# ADC_AFE.net
KiCad netlist of a schematic drawn in Altium Designer
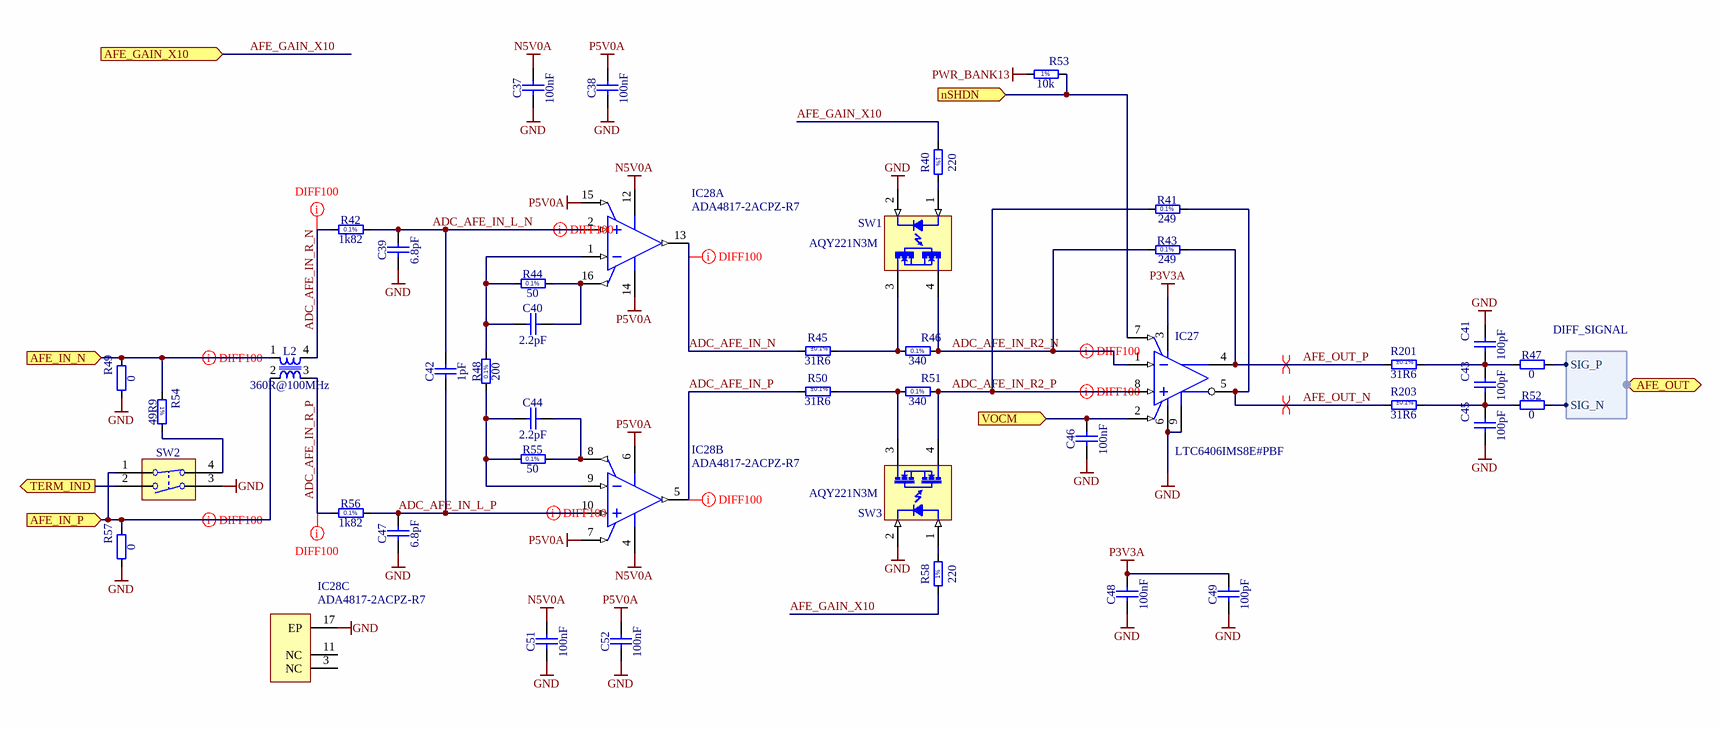
[diagram p0: ADC_AFE.SchDoc]

(export (version "E")
  (design (tool "Eeschema 10.0.6"))
  (components
    (comp (ref "C37")
      (value "100nF")
      (footprint "CAPC1005X55N")
      (description "Non-polarised capacitor")
      (fields
        (field (name "PART NUMBER") "CC0402_100NF_16V_10%_X7R")
        (field (name "VOLTAGE") "16V")
        (field (name "AUTHOR") "CERN DEM JLC")
      )
      (libsource (lib "Capacitors") (part "Capacitor - non polarized"))
    )
    (comp (ref "C38")
      (value "100nF")
      (footprint "CAPC1005X55N")
      (description "Non-polarised capacitor")
      (fields
        (field (name "PART NUMBER") "CC0402_100NF_16V_10%_X7R")
        (field (name "VOLTAGE") "16V")
        (field (name "AUTHOR") "CERN DEM JLC")
      )
      (libsource (lib "Capacitors") (part "Capacitor - non polarized"))
    )
    (comp (ref "C39")
      (value "6.8pF")
      (footprint "CAPC1005X61N")
      (description "Non-polarised capacitor")
      (fields
        (field (name "PART NUMBER") "CC0402_6.8PF_50V_0.1PF_NP0_JOHANSON_R07S")
        (field (name "VOLTAGE") "50V")
        (field (name "AUTHOR") "CERN DEM BC")
      )
      (libsource (lib "Capacitors") (part "Capacitor - non polarized"))
    )
    (comp (ref "C40")
      (value "2.2pF")
      (footprint "CAPC1608X87N")
      (description "Non-polarised capacitor")
      (fields
        (field (name "PART NUMBER") "CC0603_2.2PF_50V_0.25PF_NP0")
        (field (name "VOLTAGE") "50V")
        (field (name "AUTHOR") "CERN DEM JLC")
      )
      (libsource (lib "Capacitors") (part "Capacitor - non polarized"))
    )
    (comp (ref "C41")
      (value "100pF")
      (footprint "CAPC1005X55N")
      (description "Non-polarised capacitor")
      (fields
        (field (name "PART NUMBER") "CC0402_100PF_50V_2%_C0G")
        (field (name "VOLTAGE") "50V")
        (field (name "AUTHOR") "CERN DEM BC")
      )
      (libsource (lib "Capacitors") (part "Capacitor - non polarized"))
    )
    (comp (ref "C42")
      (value "1pF")
      (footprint "CAPC1005X55N")
      (description "Non-polarised capacitor")
      (fields
        (field (name "PART NUMBER") "CC0402_1PF_50V_0.25PF_C0G")
        (field (name "VOLTAGE") "50V")
        (field (name "AUTHOR") "CERN DEM JLC")
      )
      (libsource (lib "Capacitors") (part "Capacitor - non polarized"))
    )
    (comp (ref "C43")
      (value "100pF")
      (footprint "CAPC1005X55N")
      (description "Non-polarised capacitor")
      (fields
        (field (name "PART NUMBER") "CC0402_100PF_50V_2%_C0G")
        (field (name "VOLTAGE") "50V")
        (field (name "AUTHOR") "CERN DEM BC")
      )
      (libsource (lib "Capacitors") (part "Capacitor - non polarized"))
    )
    (comp (ref "C44")
      (value "2.2pF")
      (footprint "CAPC1608X87N")
      (description "Non-polarised capacitor")
      (fields
        (field (name "PART NUMBER") "CC0603_2.2PF_50V_0.25PF_NP0")
        (field (name "VOLTAGE") "50V")
        (field (name "AUTHOR") "CERN DEM JLC")
      )
      (libsource (lib "Capacitors") (part "Capacitor - non polarized"))
    )
    (comp (ref "C45")
      (value "100pF")
      (footprint "CAPC1005X55N")
      (description "Non-polarised capacitor")
      (fields
        (field (name "PART NUMBER") "CC0402_100PF_50V_2%_C0G")
        (field (name "VOLTAGE") "50V")
        (field (name "AUTHOR") "CERN DEM BC")
      )
      (libsource (lib "Capacitors") (part "Capacitor - non polarized"))
    )
    (comp (ref "C46")
      (value "100nF")
      (footprint "CAPC1005X55N")
      (description "Non-polarised capacitor")
      (fields
        (field (name "PART NUMBER") "CC0402_100NF_16V_10%_X7R")
        (field (name "VOLTAGE") "16V")
        (field (name "AUTHOR") "CERN DEM JLC")
      )
      (libsource (lib "Capacitors") (part "Capacitor - non polarized"))
    )
    (comp (ref "C47")
      (value "6.8pF")
      (footprint "CAPC1005X61N")
      (description "Non-polarised capacitor")
      (fields
        (field (name "PART NUMBER") "CC0402_6.8PF_50V_0.1PF_NP0_JOHANSON_R07S")
        (field (name "VOLTAGE") "50V")
        (field (name "AUTHOR") "CERN DEM BC")
      )
      (libsource (lib "Capacitors") (part "Capacitor - non polarized"))
    )
    (comp (ref "C48")
      (value "100nF")
      (footprint "CAPC1005X55N")
      (description "Non-polarised capacitor")
      (fields
        (field (name "PART NUMBER") "CC0402_100NF_16V_10%_X7R")
        (field (name "VOLTAGE") "16V")
        (field (name "AUTHOR") "CERN DEM JLC")
      )
      (libsource (lib "Capacitors") (part "Capacitor - non polarized"))
    )
    (comp (ref "C49")
      (value "100pF")
      (footprint "CAPC1005X55N")
      (description "Non-polarised capacitor")
      (fields
        (field (name "PART NUMBER") "CC0402_100PF_50V_2%_C0G")
        (field (name "VOLTAGE") "50V")
        (field (name "AUTHOR") "CERN DEM BC")
      )
      (libsource (lib "Capacitors") (part "Capacitor - non polarized"))
    )
    (comp (ref "C51")
      (value "100nF")
      (footprint "CAPC1005X55N")
      (description "Non-polarised capacitor")
      (fields
        (field (name "PART NUMBER") "CC0402_100NF_16V_10%_X7R")
        (field (name "VOLTAGE") "16V")
        (field (name "AUTHOR") "CERN DEM JLC")
      )
      (libsource (lib "Capacitors") (part "Capacitor - non polarized"))
    )
    (comp (ref "C52")
      (value "100nF")
      (footprint "CAPC1005X55N")
      (description "Non-polarised capacitor")
      (fields
        (field (name "PART NUMBER") "CC0402_100NF_16V_10%_X7R")
        (field (name "VOLTAGE") "16V")
        (field (name "AUTHOR") "CERN DEM JLC")
      )
      (libsource (lib "Capacitors") (part "Capacitor - non polarized"))
    )
    (comp (ref "IC27")
      (value "LTC6406IMS8E#PBF")
      (footprint "LT-MS8E-8-EDP_M")
      (fields
        (field (name "LINEAR TECHNOLOGY PART NUMBER") "LTC6406")
        (field (name "MANUFACTURER") "Linear Technology")
      )
      (libsource (lib "Altium Content Vault") (part "LT-LTC6406-MS8E-8"))
    )
    (comp (ref "IC28")
      (value "ADA4817-2ACPZ-R7")
      (footprint "CP-16-4_N")
      (fields (field (name "GENERIC PART NUMBER") "ADA4817-2") (field (name "MANUFACTURER") "Analog Devices"))
      (libsource (lib "") (part "ADI-ADA4817-2-CP-16-4_1"))
    )
    (comp (ref "L2")
      (value "360R@100MHz")
      (footprint "IND_TDK_ACM2012")
      (description "Inductor Common Mode")
      (fields
        (field (name "PART NUMBER") "IND_TDK_ACM2012-361-2P")
        (field (name "POWER") "220mA")
        (field (name "AUTHOR") "CERN DEM BC")
      )
      (libsource (lib "Inductors & Transformers") (part "Inductor Common Mode 1-4 2-3"))
    )
    (comp (ref "R40")
      (value "220")
      (footprint "RESC1608X55N")
      (description "Resistor - 1%")
      (fields
        (field (name "MANUFACTURER1 PART NUMBER") "NRC06F2200TRF")
        (field (name "MANUFACTURER") "GENERIC")
        (field (name "AUTHOR") "CERN DEM JLC")
      )
      (libsource (lib "Resistors") (part "Resistor - 1%"))
    )
    (comp (ref "R41")
      (value "249")
      (footprint "RESC1608X55N")
      (description "Resistor - 0.1%")
      (fields
        (field (name "PART NUMBER") "R0603_249R_0.1%_0.063W_10PPM")
        (field (name "POWER") "0.063W")
        (field (name "AUTHOR") "CERN DEM JLC")
      )
      (libsource (lib "") (part "Resistor - 0.1%_1"))
    )
    (comp (ref "R42")
      (value "1k82")
      (footprint "RESC1608X55N")
      (description "Resistor - 0.1%")
      (fields
        (field (name "PART NUMBER") "R0603_1K82_0.1%_0.063W_10PPM")
        (field (name "POWER") "0.063W")
        (field (name "AUTHOR") "CERN DEM JLC")
      )
      (libsource (lib "") (part "Resistor - 0.1%_1"))
    )
    (comp (ref "R43")
      (value "249")
      (footprint "RESC1608X55N")
      (description "Resistor - 0.1%")
      (fields
        (field (name "PART NUMBER") "R0603_249R_0.1%_0.063W_10PPM")
        (field (name "POWER") "0.063W")
        (field (name "AUTHOR") "CERN DEM JLC")
      )
      (libsource (lib "") (part "Resistor - 0.1%_1"))
    )
    (comp (ref "R44")
      (value "50")
      (footprint "RESC1005X35N")
      (description "Resistor - 0.1%")
      (fields
        (field (name "PART NUMBER") "R0402_50R_0.1%_0.05W_25PPM")
        (field (name "POWER") "0.05W")
        (field (name "AUTHOR") "CERN DEM JMW")
      )
      (libsource (lib "Resistors") (part "Resistor - 0.1%"))
    )
    (comp (ref "R45")
      (value "31R6")
      (footprint "RESC1608X55N")
      (description "Resistor - 0.1%")
      (fields
        (field (name "PART NUMBER") "R0603_31R6_0.1%_0.063W_10PPM")
        (field (name "POWER") "0.063W")
        (field (name "TOLERANCE") "±0.1%")
        (field (name "AUTHOR") "CERN DEM JLC")
      )
      (libsource (lib "") (part "Resistor - 0.1%_1"))
    )
    (comp (ref "R46")
      (value "340")
      (footprint "RESC1608X55N")
      (description "Resistor - 0.1%")
      (fields
        (field (name "PART NUMBER") "R0603_340R_0.1%_0.063W_10PPM")
        (field (name "POWER") "0.063W")
        (field (name "AUTHOR") "CERN DEM JLC")
      )
      (libsource (lib "") (part "Resistor - 0.1%_1"))
    )
    (comp (ref "R47")
      (value "0")
      (footprint "RESC1005X40N")
      (description "Resistor")
      (fields
        (field (name "PART NUMBER") "R0402_0R_JUMPER")
        (field (name "MANUFACTURER") "GENERIC")
        (field (name "AUTHOR") "CERN DEM JLC")
      )
      (libsource (lib "Resistors") (part "Resistor"))
    )
    (comp (ref "R48")
      (value "200")
      (footprint "RESC1608X55N")
      (description "Resistor - 0.1%")
      (fields
        (field (name "PART NUMBER") "R0603_200R_0.1%_0.063W_10PPM")
        (field (name "POWER") "0.063W")
        (field (name "AUTHOR") "CERN DEM JLC")
      )
      (libsource (lib "") (part "Resistor - 0.1%_1"))
    )
    (comp (ref "R49")
      (value "0")
      (footprint "RESC1005X40N")
      (description "Resistor")
      (fields
        (field (name "PART NUMBER") "R0402_0R_JUMPER")
        (field (name "MANUFACTURER") "GENERIC")
        (field (name "AUTHOR") "CERN DEM JLC")
      )
      (libsource (lib "Resistors") (part "Resistor"))
    )
    (comp (ref "R50")
      (value "31R6")
      (footprint "RESC1608X55N")
      (description "Resistor - 0.1%")
      (fields
        (field (name "PART NUMBER") "R0603_31R6_0.1%_0.063W_10PPM")
        (field (name "POWER") "0.063W")
        (field (name "TOLERANCE") "±0.1%")
        (field (name "AUTHOR") "CERN DEM JLC")
      )
      (libsource (lib "") (part "Resistor - 0.1%_1"))
    )
    (comp (ref "R51")
      (value "340")
      (footprint "RESC1608X55N")
      (description "Resistor - 0.1%")
      (fields
        (field (name "PART NUMBER") "R0603_340R_0.1%_0.063W_10PPM")
        (field (name "POWER") "0.063W")
        (field (name "AUTHOR") "CERN DEM JLC")
      )
      (libsource (lib "") (part "Resistor - 0.1%_1"))
    )
    (comp (ref "R52")
      (value "0")
      (footprint "RESC1005X40N")
      (description "Resistor")
      (fields
        (field (name "PART NUMBER") "R0402_0R_JUMPER")
        (field (name "MANUFACTURER") "GENERIC")
        (field (name "AUTHOR") "CERN DEM JLC")
      )
      (libsource (lib "Resistors") (part "Resistor"))
    )
    (comp (ref "R53")
      (value "10k")
      (footprint "RESC1005X40N")
      (description "Resistor - 1%")
      (fields
        (field (name "PART NUMBER") "R0402_10K_1%_0.0625W_100PPM")
        (field (name "POWER") "0.0625W")
        (field (name "AUTHOR") "CERN DEM JLC")
      )
      (libsource (lib "Resistors") (part "Resistor - 1%"))
    )
    (comp (ref "R54")
      (value "49R9")
      (footprint "RESC6331X70N")
      (description "Resistor - 1%")
      (fields
        (field (name "PART NUMBER") "R2512_49R9_1%_1W_100PPM_VISHAY_CRCW")
        (field (name "POWER") "1W")
        (field (name "AUTHOR") "CERN DEM JLC")
      )
      (libsource (lib "Resistors") (part "Resistor - 1%"))
    )
    (comp (ref "R55")
      (value "50")
      (footprint "RESC1005X35N")
      (description "Resistor - 0.1%")
      (fields
        (field (name "PART NUMBER") "R0402_50R_0.1%_0.05W_25PPM")
        (field (name "POWER") "0.05W")
        (field (name "AUTHOR") "CERN DEM JMW")
      )
      (libsource (lib "Resistors") (part "Resistor - 0.1%"))
    )
    (comp (ref "R56")
      (value "1k82")
      (footprint "RESC1608X55N")
      (description "Resistor - 0.1%")
      (fields
        (field (name "PART NUMBER") "R0603_1K82_0.1%_0.063W_10PPM")
        (field (name "POWER") "0.063W")
        (field (name "AUTHOR") "CERN DEM JLC")
      )
      (libsource (lib "") (part "Resistor - 0.1%_1"))
    )
    (comp (ref "R57")
      (value "0")
      (footprint "RESC1005X40N")
      (description "Resistor")
      (fields
        (field (name "PART NUMBER") "R0402_0R_JUMPER")
        (field (name "MANUFACTURER") "GENERIC")
        (field (name "AUTHOR") "CERN DEM JLC")
      )
      (libsource (lib "Resistors") (part "Resistor"))
    )
    (comp (ref "R58")
      (value "220")
      (footprint "RESC1608X55N")
      (description "Resistor - 1%")
      (fields
        (field (name "MANUFACTURER1 PART NUMBER") "NRC06F2200TRF")
        (field (name "MANUFACTURER") "GENERIC")
        (field (name "AUTHOR") "CERN DEM JLC")
      )
      (libsource (lib "Resistors") (part "Resistor - 1%"))
    )
    (comp (ref "R201")
      (value "31R6")
      (footprint "RESC1608X55N")
      (description "Resistor - 0.1%")
      (fields
        (field (name "PART NUMBER") "R0603_31R6_0.1%_0.063W_10PPM")
        (field (name "POWER") "0.063W")
        (field (name "TOLERANCE") "±0.1%")
        (field (name "AUTHOR") "CERN DEM JLC")
      )
      (libsource (lib "") (part "Resistor - 0.1%_1"))
    )
    (comp (ref "R203")
      (value "31R6")
      (footprint "RESC1608X55N")
      (description "Resistor - 0.1%")
      (fields
        (field (name "PART NUMBER") "R0603_31R6_0.1%_0.063W_10PPM")
        (field (name "POWER") "0.063W")
        (field (name "TOLERANCE") "±0.1%")
        (field (name "AUTHOR") "CERN DEM JLC")
      )
      (libsource (lib "") (part "Resistor - 0.1%_1"))
    )
    (comp (ref "SW1")
      (value "AQY221N3M")
      (footprint "PANASONIC_AQY22(SON)")
      (description "PhotoMOS Relay")
      (fields (field (name "MANUFACTURER") "PANASONIC") (field (name "AUTHOR") "CERN DEM JLC"))
      (libsource (lib "ICs And Semiconductors") (part "PhotoMOS Relay x1 Type2"))
    )
    (comp (ref "SW2")
      (value "Switch")
      (footprint "SW_CTS_204-121ST")
      (description "2x SPST DIP Switch 1NO + 1NF")
      (fields
        (field (name "PART NUMBER") "SW_CTS_204-121ST")
        (field (name "MANUFACTURER") "CTS")
        (field (name "AUTHOR") "CERN DEM JLC")
      )
      (libsource (lib "Eletro-mechanical") (part "SW_CTS_204-121ST"))
    )
    (comp (ref "SW3")
      (value "AQY221N3M")
      (footprint "PANASONIC_AQY22(SON)")
      (description "PhotoMOS Relay")
      (fields (field (name "MANUFACTURER") "PANASONIC") (field (name "AUTHOR") "CERN DEM JLC"))
      (libsource (lib "") (part "PhotoMOS Relay x1 Type2_1"))
    )
  )
  (nets
    (net (code "2") (name "/ADC_AFE_IN_L_N") (class "Default")
      (node (ref "C39") (pin "2") (pinfunction "2_2") (pintype "passive"))
      (node (ref "C42") (pin "2") (pinfunction "2_2") (pintype "passive"))
      (node (ref "IC28") (pin "2") (pinfunction "+IN_1_2") (pintype "input"))
      (node (ref "R42") (pin "2") (pinfunction "2_2") (pintype "passive"))
    )
    (net (code "3") (name "/ADC_AFE_IN_L_P") (class "Default")
      (node (ref "C42") (pin "1") (pinfunction "1_1") (pintype "passive"))
      (node (ref "C47") (pin "2") (pinfunction "2_2") (pintype "passive"))
      (node (ref "IC28") (pin "10") (pinfunction "+IN_2_10") (pintype "input"))
      (node (ref "R56") (pin "2") (pinfunction "2_2") (pintype "passive"))
    )
    (net (code "4") (name "/ADC_AFE_IN_N") (class "Default")
      (node (ref "IC28") (pin "13") (pinfunction "OUT_1_13") (pintype "output"))
      (node (ref "R45") (pin "1") (pinfunction "1_1") (pintype "passive"))
    )
    (net (code "5") (name "/ADC_AFE_IN_P") (class "Default")
      (node (ref "IC28") (pin "5") (pinfunction "OUT_2_5") (pintype "output"))
      (node (ref "R50") (pin "1") (pinfunction "1_1") (pintype "passive"))
    )
    (net (code "6") (name "/ADC_AFE_IN_R2_N") (class "Default")
      (node (ref "IC27") (pin "1") (pinfunction "-IN_1") (pintype "input"))
      (node (ref "R43") (pin "1") (pinfunction "1_1") (pintype "passive"))
      (node (ref "R46") (pin "2") (pinfunction "2_2") (pintype "passive"))
      (node (ref "SW1") (pin "4") (pinfunction "E_4") (pintype "open_emitter"))
    )
    (net (code "7") (name "/ADC_AFE_IN_R2_P") (class "Default")
      (node (ref "IC27") (pin "8") (pinfunction "+IN_8") (pintype "input"))
      (node (ref "R41") (pin "1") (pinfunction "1_1") (pintype "passive"))
      (node (ref "R51") (pin "2") (pinfunction "2_2") (pintype "passive"))
      (node (ref "SW3") (pin "4") (pinfunction "E_4") (pintype "open_emitter"))
    )
    (net (code "8") (name "/ADC_AFE_IN_R_N") (class "Default")
      (node (ref "L2") (pin "4") (pinfunction "4_4") (pintype "passive"))
      (node (ref "R42") (pin "1") (pinfunction "1_1") (pintype "passive"))
    )
    (net (code "9") (name "/ADC_AFE_IN_R_P") (class "Default")
      (node (ref "L2") (pin "3") (pinfunction "3_3") (pintype "passive"))
      (node (ref "R56") (pin "1") (pinfunction "1_1") (pintype "passive"))
    )
    (net (code "10") (name "/AFE_GAIN_X10") (class "Default")
      (node (ref "R40") (pin "1") (pinfunction "1_1") (pintype "passive"))
      (node (ref "R58") (pin "1") (pinfunction "1_1") (pintype "passive"))
    )
    (net (code "11") (name "/AFE_IN_N") (class "Default")
      (node (ref "L2") (pin "1") (pinfunction "1_1") (pintype "passive"))
      (node (ref "R49") (pin "2") (pinfunction "2_2") (pintype "passive"))
      (node (ref "R54") (pin "1") (pinfunction "1_1") (pintype "passive"))
    )
    (net (code "12") (name "/AFE_IN_P") (class "Default")
      (node (ref "L2") (pin "2") (pinfunction "2_2") (pintype "passive"))
      (node (ref "R57") (pin "2") (pinfunction "2_2") (pintype "passive"))
      (node (ref "SW2") (pin "1") (pinfunction "1_1") (pintype "passive"))
    )
    (net (code "13") (name "/AFE_OUT_N") (class "Default")
      (node (ref "IC27") (pin "5") (pinfunction "-OUT_5") (pintype "tri_state"))
      (node (ref "R203") (pin "1") (pinfunction "1_1") (pintype "passive"))
      (node (ref "R41") (pin "2") (pinfunction "2_2") (pintype "passive"))
    )
    (net (code "14") (name "/AFE_OUT_P") (class "Default")
      (node (ref "IC27") (pin "4") (pinfunction "+OUT_4") (pintype "tri_state"))
      (node (ref "R201") (pin "1") (pinfunction "1_1") (pintype "passive"))
      (node (ref "R43") (pin "2") (pinfunction "2_2") (pintype "passive"))
    )
    (net (code "15") (name "/SIG_N") (class "Default")
      (node (ref "R52") (pin "2") (pinfunction "2_2") (pintype "passive"))
    )
    (net (code "16") (name "/SIG_P") (class "Default")
      (node (ref "R47") (pin "2") (pinfunction "2_2") (pintype "passive"))
    )
    (net (code "17") (name "/TERM_IND") (class "Default")
      (node (ref "SW2") (pin "2") (pinfunction "2_2") (pintype "passive"))
    )
    (net (code "18") (name "/VOCM") (class "Default")
      (node (ref "C46") (pin "2") (pinfunction "2_2") (pintype "passive"))
      (node (ref "IC27") (pin "2") (pinfunction "VOCM_2") (pintype "input"))
    )
    (net (code "19") (name "/nSHDN") (class "Default")
      (node (ref "IC27") (pin "7") (pinfunction "~{SHDN}_7") (pintype "input"))
      (node (ref "R53") (pin "2") (pinfunction "2_2") (pintype "passive"))
    )
    (net (code "21") (name "GND") (class "Default")
      (node (ref "C37") (pin "1") (pinfunction "1_1") (pintype "passive"))
      (node (ref "C38") (pin "1") (pinfunction "1_1") (pintype "passive"))
      (node (ref "C39") (pin "1") (pinfunction "1_1") (pintype "passive"))
      (node (ref "C41") (pin "2") (pinfunction "2_2") (pintype "passive"))
      (node (ref "C45") (pin "1") (pinfunction "1_1") (pintype "passive"))
      (node (ref "C46") (pin "1") (pinfunction "1_1") (pintype "passive"))
      (node (ref "C47") (pin "1") (pinfunction "1_1") (pintype "passive"))
      (node (ref "C48") (pin "1") (pinfunction "1_1") (pintype "passive"))
      (node (ref "C49") (pin "1") (pinfunction "1_1") (pintype "passive"))
      (node (ref "C51") (pin "1") (pinfunction "1_1") (pintype "passive"))
      (node (ref "C52") (pin "1") (pinfunction "1_1") (pintype "passive"))
      (node (ref "IC27") (pin "6") (pinfunction "V-_6") (pintype "power_in"))
      (node (ref "IC27") (pin "9") (pinfunction "EP_9") (pintype "power_in"))
      (node (ref "IC28") (pin "17") (pinfunction "EP_17") (pintype "passive"))
      (node (ref "R49") (pin "1") (pinfunction "1_1") (pintype "passive"))
      (node (ref "R57") (pin "1") (pinfunction "1_1") (pintype "passive"))
      (node (ref "SW1") (pin "2") (pinfunction "K_2") (pintype "input"))
      (node (ref "SW2") (pin "3") (pinfunction "3_3") (pintype "passive"))
      (node (ref "SW3") (pin "2") (pinfunction "K_2") (pintype "input"))
    )
    (net (code "22") (name "N5V0A") (class "Default")
      (node (ref "C37") (pin "2") (pinfunction "2_2") (pintype "passive"))
      (node (ref "C51") (pin "2") (pinfunction "2_2") (pintype "passive"))
      (node (ref "IC28") (pin "12") (pinfunction "-VS_1_12") (pintype "power_in"))
      (node (ref "IC28") (pin "4") (pinfunction "-VS_2_4") (pintype "power_in"))
    )
    (net (code "23") (name "Net-(C41-Pad1)") (class "Default")
      (node (ref "C41") (pin "1") (pinfunction "1_1") (pintype "passive"))
      (node (ref "C43") (pin "2") (pinfunction "2_2") (pintype "passive"))
      (node (ref "R201") (pin "2") (pinfunction "2_2") (pintype "passive"))
      (node (ref "R47") (pin "1") (pinfunction "1_1") (pintype "passive"))
    )
    (net (code "24") (name "Net-(C43-Pad1)") (class "Default")
      (node (ref "C43") (pin "1") (pinfunction "1_1") (pintype "passive"))
      (node (ref "C45") (pin "2") (pinfunction "2_2") (pintype "passive"))
      (node (ref "R203") (pin "2") (pinfunction "2_2") (pintype "passive"))
      (node (ref "R52") (pin "1") (pinfunction "1_1") (pintype "passive"))
    )
    (net (code "25") (name "Net-(IC28A--IN_1)") (class "Default")
      (node (ref "C40") (pin "1") (pinfunction "1_1") (pintype "passive"))
      (node (ref "IC28") (pin "1") (pinfunction "-IN_1_1") (pintype "input"))
      (node (ref "R44") (pin "1") (pinfunction "1_1") (pintype "passive"))
      (node (ref "R48") (pin "2") (pinfunction "2_2") (pintype "passive"))
    )
    (net (code "26") (name "Net-(IC28A-FB1)") (class "Default")
      (node (ref "C40") (pin "2") (pinfunction "2_2") (pintype "passive"))
      (node (ref "IC28") (pin "16") (pinfunction "FB1_16") (pintype "output"))
      (node (ref "R44") (pin "2") (pinfunction "2_2") (pintype "passive"))
    )
    (net (code "27") (name "Net-(IC28B--IN_2)") (class "Default")
      (node (ref "C44") (pin "1") (pinfunction "1_1") (pintype "passive"))
      (node (ref "IC28") (pin "9") (pinfunction "-IN_2_9") (pintype "input"))
      (node (ref "R48") (pin "1") (pinfunction "1_1") (pintype "passive"))
      (node (ref "R55") (pin "1") (pinfunction "1_1") (pintype "passive"))
    )
    (net (code "28") (name "Net-(IC28B-FB2)") (class "Default")
      (node (ref "C44") (pin "2") (pinfunction "2_2") (pintype "passive"))
      (node (ref "IC28") (pin "8") (pinfunction "FB2_8") (pintype "output"))
      (node (ref "R55") (pin "2") (pinfunction "2_2") (pintype "passive"))
    )
    (net (code "29") (name "Net-(R54-Pad2)") (class "Default")
      (node (ref "R54") (pin "2") (pinfunction "2_2") (pintype "passive"))
      (node (ref "SW2") (pin "4") (pinfunction "4_4") (pintype "passive"))
    )
    (net (code "30") (name "Net-(SW1-A)") (class "Default")
      (node (ref "R40") (pin "2") (pinfunction "2_2") (pintype "passive"))
      (node (ref "SW1") (pin "1") (pinfunction "A_1") (pintype "input"))
    )
    (net (code "31") (name "Net-(SW1-C)") (class "Default")
      (node (ref "R45") (pin "2") (pinfunction "2_2") (pintype "passive"))
      (node (ref "R46") (pin "1") (pinfunction "1_1") (pintype "passive"))
      (node (ref "SW1") (pin "3") (pinfunction "C_3") (pintype "open_collector"))
    )
    (net (code "32") (name "Net-(SW3-A)") (class "Default")
      (node (ref "R58") (pin "2") (pinfunction "2_2") (pintype "passive"))
      (node (ref "SW3") (pin "1") (pinfunction "A_1") (pintype "input"))
    )
    (net (code "33") (name "Net-(SW3-C)") (class "Default")
      (node (ref "R50") (pin "2") (pinfunction "2_2") (pintype "passive"))
      (node (ref "R51") (pin "1") (pinfunction "1_1") (pintype "passive"))
      (node (ref "SW3") (pin "3") (pinfunction "C_3") (pintype "open_collector"))
    )
    (net (code "34") (name "P3V3A") (class "Default")
      (node (ref "C48") (pin "2") (pinfunction "2_2") (pintype "passive"))
      (node (ref "C49") (pin "2") (pinfunction "2_2") (pintype "passive"))
      (node (ref "IC27") (pin "3") (pinfunction "V+_3") (pintype "power_in"))
    )
    (net (code "35") (name "P5V0A") (class "Default")
      (node (ref "C38") (pin "2") (pinfunction "2_2") (pintype "passive"))
      (node (ref "C52") (pin "2") (pinfunction "2_2") (pintype "passive"))
      (node (ref "IC28") (pin "14") (pinfunction "+VS_1_14") (pintype "power_in"))
      (node (ref "IC28") (pin "15") (pinfunction "~{PD1}_15") (pintype "input"))
      (node (ref "IC28") (pin "6") (pinfunction "+VS_2_6") (pintype "power_in"))
      (node (ref "IC28") (pin "7") (pinfunction "~{PD2}_7") (pintype "input"))
    )
    (net (code "36") (name "PWR_BANK13") (class "Default")
      (node (ref "R53") (pin "1") (pinfunction "1_1") (pintype "passive"))
    )
    (net (code "37") (name "unconnected-(IC28C-NC-Pad3)") (class "Default")
      (node (ref "IC28") (pin "3") (pinfunction "NC_3") (pintype "passive"))
    )
    (net (code "38") (name "unconnected-(IC28C-NC-Pad11)") (class "Default")
      (node (ref "IC28") (pin "11") (pinfunction "NC_11") (pintype "passive"))
    )
  )
)
